# COMS0001_Beacon.net
KiCad netlist of a schematic drawn in Altium Designer
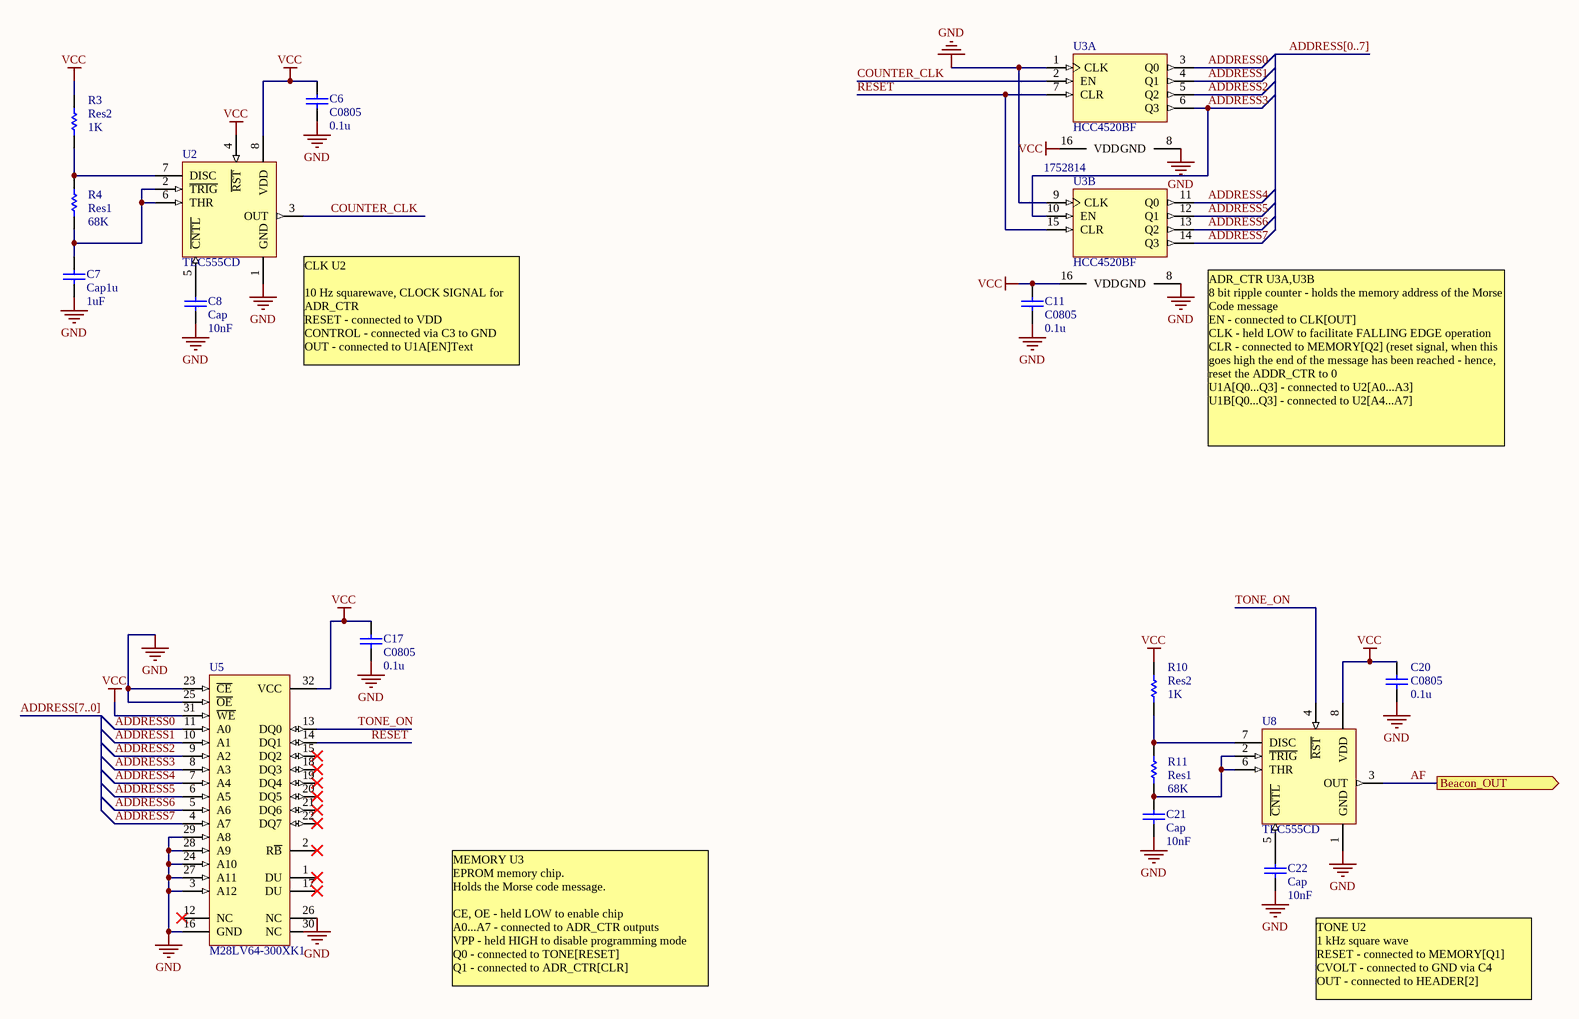
[diagram p0: COMS0001_Beacon.SchDoc]

(export (version "E")
  (design (tool "Eeschema 10.0.6"))
  (components
    (comp (ref "C6")
      (value "C0805")
      (footprint "CAPC2012M")
      (description "Capacitor")
      (fields (field (name "ALTIUM_VALUE") "0.1u") (field (name "PUBLISHER") "Altium Limited"))
      (libsource (lib "Miscellaneous Devices") (part "Cap"))
    )
    (comp (ref "C7")
      (value "Cap1u")
      (footprint "CAPC2012M")
      (description "Capacitor")
      (fields (field (name "ALTIUM_VALUE") "1uF") (field (name "PUBLISHER") "Altium Limited"))
      (libsource (lib "Miscellaneous Devices") (part "Cap"))
    )
    (comp (ref "C8")
      (value "Cap")
      (footprint "CAPC2012M")
      (description "Capacitor")
      (fields (field (name "ALTIUM_VALUE") "10nF") (field (name "PUBLISHER") "Altium Limited"))
      (libsource (lib "Miscellaneous Devices") (part "Cap"))
    )
    (comp (ref "C11")
      (value "C0805")
      (footprint "CAPC2012M")
      (description "Capacitor")
      (fields (field (name "ALTIUM_VALUE") "0.1u") (field (name "PUBLISHER") "Altium Limited"))
      (libsource (lib "Miscellaneous Devices") (part "Cap"))
    )
    (comp (ref "C17")
      (value "C0805")
      (footprint "CAPC2012M")
      (description "Capacitor")
      (fields (field (name "ALTIUM_VALUE") "0.1u") (field (name "PUBLISHER") "Altium Limited"))
      (libsource (lib "Miscellaneous Devices") (part "Cap"))
    )
    (comp (ref "C20")
      (value "C0805")
      (footprint "CAPC2012M")
      (description "Capacitor")
      (fields (field (name "ALTIUM_VALUE") "0.1u") (field (name "PUBLISHER") "Altium Limited"))
      (libsource (lib "Miscellaneous Devices") (part "Cap"))
    )
    (comp (ref "C21")
      (value "Cap")
      (footprint "CAPC2012M")
      (description "Capacitor")
      (fields (field (name "ALTIUM_VALUE") "10nF") (field (name "PUBLISHER") "Altium Limited"))
      (libsource (lib "Miscellaneous Devices") (part "Cap"))
    )
    (comp (ref "C22")
      (value "Cap")
      (footprint "CAPC2012M")
      (description "Capacitor")
      (fields (field (name "ALTIUM_VALUE") "10nF") (field (name "PUBLISHER") "Altium Limited"))
      (libsource (lib "Miscellaneous Devices") (part "Cap"))
    )
    (comp (ref "R3")
      (value "Res2")
      (footprint "RESC2012M")
      (description "Resistor")
      (fields (field (name "ALTIUM_VALUE") "1K") (field (name "PUBLISHER") "Altium Limited"))
      (libsource (lib "Miscellaneous Devices") (part "Res1"))
    )
    (comp (ref "R4")
      (value "Res1")
      (footprint "RESC2012M")
      (description "Resistor")
      (fields (field (name "ALTIUM_VALUE") "68K") (field (name "PUBLISHER") "Altium Limited"))
      (libsource (lib "Miscellaneous Devices") (part "Res1"))
    )
    (comp (ref "R10")
      (value "Res2")
      (footprint "RESC2012M")
      (description "Resistor")
      (fields (field (name "ALTIUM_VALUE") "1K") (field (name "PUBLISHER") "Altium Limited"))
      (libsource (lib "Miscellaneous Devices") (part "Res1"))
    )
    (comp (ref "R11")
      (value "Res1")
      (footprint "RESC2012M")
      (description "Resistor")
      (fields (field (name "ALTIUM_VALUE") "68K") (field (name "PUBLISHER") "Altium Limited"))
      (libsource (lib "Miscellaneous Devices") (part "Res1"))
    )
    (comp (ref "U2")
      (value "TLC555CD")
      (footprint "D008_M")
      (description "LinCMOS Timer")
      (fields (field (name "PUBLISHER") "Altium Limited"))
      (libsource (lib "TI Analog Timer Circuit") (part "TLC555CD"))
    )
    (comp (ref "U3")
      (value "HCC4520BF")
      (footprint "SOIC16_M")
      (description "Dual Binary Up-Counter")
      (fields (field (name "SUPPLIER PART NUMBER 1") "1752814") (field (name "PUBLISHER") "Altium Limited"))
      (libsource (lib "ST Logic Counter") (part "HCC4520BF"))
    )
    (comp (ref "U5")
      (value "M28LV64-300XK1")
      (footprint "PLCC32")
      (description "64K (8K x 8) Low-Voltage Parallel EEPROM with Software Data Protection")
      (fields (field (name "PUBLISHER") "Altium Limited"))
      (libsource (lib "ST Memory EEPROM Parallel") (part "M28LV64-300XK1"))
    )
    (comp (ref "U8")
      (value "TLC555CD")
      (footprint "D008_M")
      (description "LinCMOS Timer")
      (fields (field (name "PUBLISHER") "Altium Limited"))
      (libsource (lib "TI Analog Timer Circuit") (part "TLC555CD"))
    )
  )
  (nets
    (net (code "1") (name "/ADDRESS0") (class "Default")
      (node (ref "U3") (pin "3") (pinfunction "Q0_3") (pintype "output"))
      (node (ref "U5") (pin "11") (pinfunction "A0_11") (pintype "input"))
    )
    (net (code "2") (name "/ADDRESS1") (class "Default")
      (node (ref "U3") (pin "4") (pinfunction "Q1_4") (pintype "output"))
      (node (ref "U5") (pin "10") (pinfunction "A1_10") (pintype "input"))
    )
    (net (code "3") (name "/ADDRESS2") (class "Default")
      (node (ref "U3") (pin "5") (pinfunction "Q2_5") (pintype "output"))
      (node (ref "U5") (pin "9") (pinfunction "A2_9") (pintype "input"))
    )
    (net (code "4") (name "/ADDRESS3") (class "Default")
      (node (ref "U3") (pin "10") (pinfunction "EN_10") (pintype "input"))
      (node (ref "U3") (pin "6") (pinfunction "Q3_6") (pintype "output"))
      (node (ref "U5") (pin "8") (pinfunction "A3_8") (pintype "input"))
    )
    (net (code "5") (name "/ADDRESS4") (class "Default")
      (node (ref "U3") (pin "11") (pinfunction "Q0_11") (pintype "output"))
      (node (ref "U5") (pin "7") (pinfunction "A4_7") (pintype "input"))
    )
    (net (code "6") (name "/ADDRESS5") (class "Default")
      (node (ref "U3") (pin "12") (pinfunction "Q1_12") (pintype "output"))
      (node (ref "U5") (pin "6") (pinfunction "A5_6") (pintype "input"))
    )
    (net (code "7") (name "/ADDRESS6") (class "Default")
      (node (ref "U3") (pin "13") (pinfunction "Q2_13") (pintype "output"))
      (node (ref "U5") (pin "5") (pinfunction "A6_5") (pintype "input"))
    )
    (net (code "8") (name "/ADDRESS7") (class "Default")
      (node (ref "U3") (pin "14") (pinfunction "Q3_14") (pintype "output"))
      (node (ref "U5") (pin "4") (pinfunction "A7_4") (pintype "input"))
    )
    (net (code "11") (name "/AF") (class "Default")
      (node (ref "U8") (pin "3") (pinfunction "OUT_3") (pintype "output"))
    )
    (net (code "12") (name "/COUNTER_CLK") (class "Default")
      (node (ref "U2") (pin "3") (pinfunction "OUT_3") (pintype "output"))
      (node (ref "U3") (pin "2") (pinfunction "EN_2") (pintype "input"))
    )
    (net (code "13") (name "/RESET") (class "Default")
      (node (ref "U3") (pin "15") (pinfunction "CLR_15") (pintype "input"))
      (node (ref "U3") (pin "7") (pinfunction "CLR_7") (pintype "input"))
      (node (ref "U5") (pin "14") (pinfunction "DQ1_14") (pintype "bidirectional"))
    )
    (net (code "14") (name "/TONE_ON") (class "Default")
      (node (ref "U5") (pin "13") (pinfunction "DQ0_13") (pintype "bidirectional"))
      (node (ref "U8") (pin "4") (pinfunction "~{RST}_4") (pintype "input"))
    )
    (net (code "15") (name "GND") (class "Default")
      (node (ref "C11") (pin "1") (pinfunction "1_1") (pintype "passive"))
      (node (ref "C17") (pin "1") (pinfunction "1_1") (pintype "passive"))
      (node (ref "C20") (pin "1") (pinfunction "1_1") (pintype "passive"))
      (node (ref "C21") (pin "1") (pinfunction "1_1") (pintype "passive"))
      (node (ref "C22") (pin "1") (pinfunction "1_1") (pintype "passive"))
      (node (ref "C6") (pin "1") (pinfunction "1_1") (pintype "passive"))
      (node (ref "C7") (pin "1") (pinfunction "1_1") (pintype "passive"))
      (node (ref "C8") (pin "1") (pinfunction "1_1") (pintype "passive"))
      (node (ref "U2") (pin "1") (pinfunction "GND_1") (pintype "power_in"))
      (node (ref "U3") (pin "1") (pinfunction "CLK_1") (pintype "input"))
      (node (ref "U3") (pin "8") (pinfunction "GND_8") (pintype "power_in"))
      (node (ref "U3") (pin "9") (pinfunction "CLK_9") (pintype "input"))
      (node (ref "U5") (pin "16") (pinfunction "GND_16") (pintype "power_in"))
      (node (ref "U5") (pin "23") (pinfunction "~{CE}_23") (pintype "input"))
      (node (ref "U5") (pin "24") (pinfunction "A10_24") (pintype "input"))
      (node (ref "U5") (pin "25") (pinfunction "~{OE}_25") (pintype "input"))
      (node (ref "U5") (pin "26") (pinfunction "NC_26") (pintype "passive"))
      (node (ref "U5") (pin "27") (pinfunction "A11_27") (pintype "input"))
      (node (ref "U5") (pin "28") (pinfunction "A9_28") (pintype "input"))
      (node (ref "U5") (pin "29") (pinfunction "A8_29") (pintype "input"))
      (node (ref "U5") (pin "3") (pinfunction "A12_3") (pintype "input"))
      (node (ref "U8") (pin "1") (pinfunction "GND_1") (pintype "power_in"))
    )
    (net (code "16") (name "Net-(U2-DISC)") (class "Default")
      (node (ref "R3") (pin "1") (pinfunction "1_1") (pintype "passive"))
      (node (ref "R4") (pin "2") (pinfunction "2_2") (pintype "passive"))
      (node (ref "U2") (pin "7") (pinfunction "DISC_7") (pintype "open_collector"))
    )
    (net (code "17") (name "Net-(U2-THR)") (class "Default")
      (node (ref "C7") (pin "2") (pinfunction "2_2") (pintype "passive"))
      (node (ref "R4") (pin "1") (pinfunction "1_1") (pintype "passive"))
      (node (ref "U2") (pin "2") (pinfunction "~{TRIG}_2") (pintype "input"))
      (node (ref "U2") (pin "6") (pinfunction "THR_6") (pintype "input"))
    )
    (net (code "18") (name "Net-(U2-~{CNTL})") (class "Default")
      (node (ref "C8") (pin "2") (pinfunction "2_2") (pintype "passive"))
      (node (ref "U2") (pin "5") (pinfunction "~{CNTL}_5") (pintype "input"))
    )
    (net (code "19") (name "Net-(U8-DISC)") (class "Default")
      (node (ref "R10") (pin "1") (pinfunction "1_1") (pintype "passive"))
      (node (ref "R11") (pin "2") (pinfunction "2_2") (pintype "passive"))
      (node (ref "U8") (pin "7") (pinfunction "DISC_7") (pintype "open_collector"))
    )
    (net (code "20") (name "Net-(U8-THR)") (class "Default")
      (node (ref "C21") (pin "2") (pinfunction "2_2") (pintype "passive"))
      (node (ref "R11") (pin "1") (pinfunction "1_1") (pintype "passive"))
      (node (ref "U8") (pin "2") (pinfunction "~{TRIG}_2") (pintype "input"))
      (node (ref "U8") (pin "6") (pinfunction "THR_6") (pintype "input"))
    )
    (net (code "21") (name "Net-(U8-~{CNTL})") (class "Default")
      (node (ref "C22") (pin "2") (pinfunction "2_2") (pintype "passive"))
      (node (ref "U8") (pin "5") (pinfunction "~{CNTL}_5") (pintype "input"))
    )
    (net (code "22") (name "VCC") (class "Default")
      (node (ref "C11") (pin "2") (pinfunction "2_2") (pintype "passive"))
      (node (ref "C17") (pin "2") (pinfunction "2_2") (pintype "passive"))
      (node (ref "C20") (pin "2") (pinfunction "2_2") (pintype "passive"))
      (node (ref "C6") (pin "2") (pinfunction "2_2") (pintype "passive"))
      (node (ref "R10") (pin "2") (pinfunction "2_2") (pintype "passive"))
      (node (ref "R3") (pin "2") (pinfunction "2_2") (pintype "passive"))
      (node (ref "U2") (pin "4") (pinfunction "~{RST}_4") (pintype "input"))
      (node (ref "U2") (pin "8") (pinfunction "VDD_8") (pintype "power_in"))
      (node (ref "U3") (pin "16") (pinfunction "VDD_16") (pintype "power_in"))
      (node (ref "U5") (pin "31") (pinfunction "~{WE}_31") (pintype "input"))
      (node (ref "U5") (pin "32") (pinfunction "VCC_32") (pintype "power_in"))
      (node (ref "U8") (pin "8") (pinfunction "VDD_8") (pintype "power_in"))
    )
    (net (code "23") (name "unconnected-(U5-DQ2-Pad15)") (class "Default")
      (node (ref "U5") (pin "15") (pinfunction "DQ2_15") (pintype "bidirectional+no_connect"))
    )
    (net (code "24") (name "unconnected-(U5-DQ3-Pad18)") (class "Default")
      (node (ref "U5") (pin "18") (pinfunction "DQ3_18") (pintype "bidirectional+no_connect"))
    )
    (net (code "25") (name "unconnected-(U5-DQ4-Pad19)") (class "Default")
      (node (ref "U5") (pin "19") (pinfunction "DQ4_19") (pintype "bidirectional+no_connect"))
    )
    (net (code "26") (name "unconnected-(U5-DQ5-Pad20)") (class "Default")
      (node (ref "U5") (pin "20") (pinfunction "DQ5_20") (pintype "bidirectional+no_connect"))
    )
    (net (code "27") (name "unconnected-(U5-DQ6-Pad21)") (class "Default")
      (node (ref "U5") (pin "21") (pinfunction "DQ6_21") (pintype "bidirectional+no_connect"))
    )
    (net (code "28") (name "unconnected-(U5-DQ7-Pad22)") (class "Default")
      (node (ref "U5") (pin "22") (pinfunction "DQ7_22") (pintype "bidirectional+no_connect"))
    )
    (net (code "29") (name "unconnected-(U5-DU-Pad1)") (class "Default")
      (node (ref "U5") (pin "1") (pinfunction "DU_1") (pintype "passive+no_connect"))
    )
    (net (code "30") (name "unconnected-(U5-DU-Pad17)") (class "Default")
      (node (ref "U5") (pin "17") (pinfunction "DU_17") (pintype "passive+no_connect"))
    )
    (net (code "31") (name "unconnected-(U5-NC-Pad12)") (class "Default")
      (node (ref "U5") (pin "12") (pinfunction "NC_12") (pintype "passive+no_connect"))
    )
    (net (code "32") (name "unconnected-(U5-NC-Pad30)") (class "Default")
      (node (ref "U5") (pin "30") (pinfunction "NC_30") (pintype "passive"))
    )
    (net (code "33") (name "unconnected-(U5-R~{B}-Pad2)") (class "Default")
      (node (ref "U5") (pin "2") (pinfunction "R~{B}_2") (pintype "passive+no_connect"))
    )
  )
)
